# pre_amp.net
KiCad netlist of a schematic drawn in Altium Designer
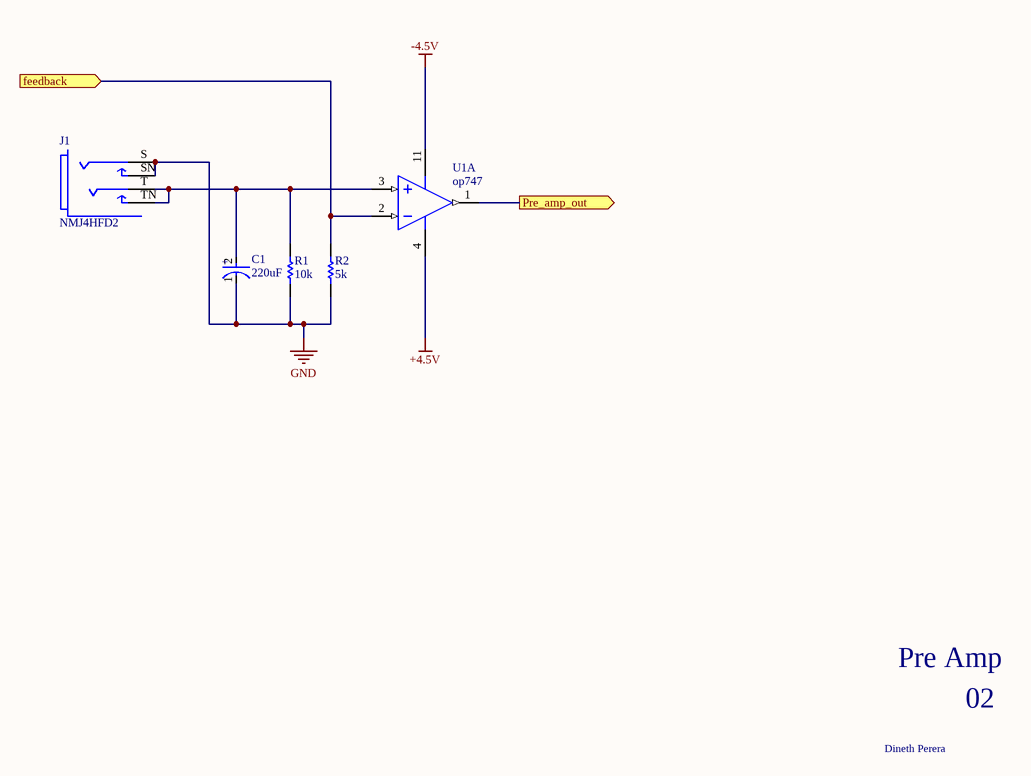
[diagram p0: pre_amp.SchDoc]

(export (version "E")
  (design (tool "Eeschema 10.0.6"))
  (components
    (comp (ref "C1")
      (value "220uF")
      (footprint "FP-FTF-MFG")
      (description "CAP ALUM 220UF 20% 50V SMD")
      (fields (field (name "TOLERANCE") "20%") (field (name "VOLTAGE") "50V"))
      (libsource (lib "Altium Content Vault") (part "203bc49f2ac43e59fd269a8c329ed05"))
    )
    (comp (ref "J1")
      (value "NMJ4HFD2")
      (footprint "FP-NMJ4HFD2-MFG")
      (description "Conn 1/4\" Mono Jack F 3 POS Solder RA Thru-Hole 3 Terminal 1 Port")
      (fields
        (field (name "MANUFACTURER") "Neutrik")
        (field (name "OCTOPART") "https://octopart.com/nmj4hfd2-neutrik-758952")
      )
      (libsource (lib "Altium Content Vault") (part "8c9933f05338f077543a5425baeefa5"))
    )
    (comp (ref "R1")
      (value "10k")
      (footprint "RESC2013X60X35NL10T20")
      (description "Chip Resistor, 10 KOhm, +/- 1%, 0.125 W, -55 to 155 degC, 0805 (2012 Metric), RoHS, Tape and Reel")
      (fields (field (name "MANUFACTURER") "Yageo"))
      (libsource (lib "Altium Content Vault") (part "RES-2"))
    )
    (comp (ref "R2")
      (value "5k")
      (footprint "RESC2013X50X30ML20T20")
      (fields (field (name "PART NUMBER") "CRCW08055K00FKTA") (field (name "MANUFACTURER") "Vishay Dale"))
      (libsource (lib "Altium Content Vault") (part "RES"))
    )
    (comp (ref "U1")
      (value "op747")
      (footprint "ADI-R-14_N")
      (fields
        (field (name "MANUFACTURER") "Analog Devices")
        (field (name "GENERIC PART NUMBER") "OP747")
        (field (name "PARTNUMBER") "OP747ARZ-REEL7")
      )
      (libsource (lib "Altium Content Vault") (part "ADI-ADxxxx_OPxxxx-X-14"))
    )
  )
  (nets
    (net (code "1") (name "+4.5V") (class "Default")
      (node (ref "U1") (pin "4") (pinfunction "+V_4") (pintype "power_in"))
    )
    (net (code "2") (name "-4.5V") (class "Default")
      (node (ref "U1") (pin "11") (pinfunction "-V_11") (pintype "power_in"))
    )
    (net (code "3") (name "/Pre_amp_out") (class "Default")
      (node (ref "U1") (pin "1") (pinfunction "OUT_A_1") (pintype "output"))
    )
    (net (code "4") (name "/feedback") (class "Default")
      (node (ref "R2") (pin "2") (pinfunction "2_2") (pintype "passive"))
      (node (ref "U1") (pin "2") (pinfunction "-IN_A_2") (pintype "input"))
    )
    (net (code "5") (name "GND") (class "Default")
      (node (ref "C1") (pin "1") (pinfunction "C_1") (pintype "passive"))
      (node (ref "J1") (pin "S") (pinfunction "S_S") (pintype "passive"))
      (node (ref "J1") (pin "SN") (pinfunction "SN_SN") (pintype "passive"))
      (node (ref "R1") (pin "1") (pinfunction "1_1") (pintype "passive"))
      (node (ref "R2") (pin "1") (pinfunction "1_1") (pintype "passive"))
    )
    (net (code "6") (name "Net-(C1-A)") (class "Default")
      (node (ref "C1") (pin "2") (pinfunction "A_2") (pintype "passive"))
      (node (ref "J1") (pin "T") (pinfunction "T_T") (pintype "passive"))
      (node (ref "J1") (pin "TN") (pinfunction "TN_TN") (pintype "passive"))
      (node (ref "R1") (pin "2") (pinfunction "2_2") (pintype "passive"))
      (node (ref "U1") (pin "3") (pinfunction "+IN_A_3") (pintype "input"))
    )
  )
)
